# RTC.net
KiCad netlist of a schematic drawn in Altium Designer
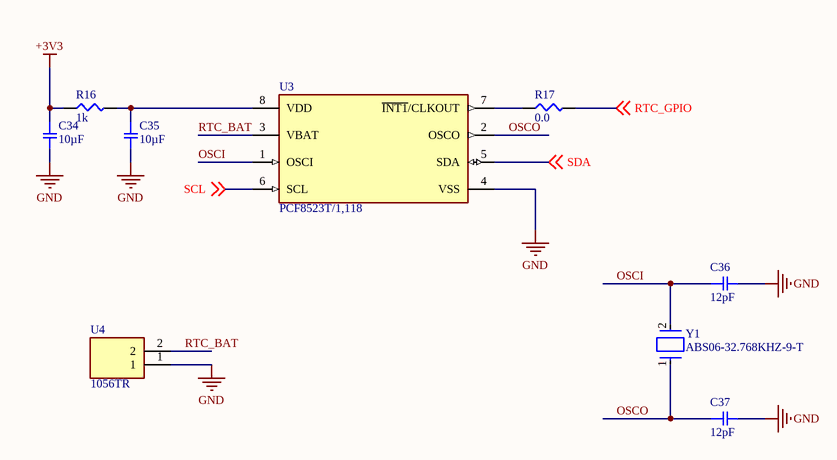
[diagram p0: RTC.SchDoc]

(export (version "E")
  (design (tool "Eeschema 10.0.6"))
  (components
    (comp (ref "C34")
      (value "10µF")
      (footprint "SMD-0402C")
      (description "CAP CER 10UF 6.3V X5R 0402")
      (fields
        (field (name "DIGI-KEY PART NUMBER") "490-13211-1-ND")
        (field (name "PART NUMBER") "GRJ155R60J106ME11D")
      )
      (libsource (lib "capacitor_murata_0402") (part "GRJ155R60J106ME11D"))
    )
    (comp (ref "C35")
      (value "10µF")
      (footprint "SMD-0402C")
      (description "CAP CER 10UF 6.3V X5R 0402")
      (fields
        (field (name "DIGI-KEY PART NUMBER") "490-13211-1-ND")
        (field (name "PART NUMBER") "GRJ155R60J106ME11D")
      )
      (libsource (lib "capacitor_murata_0402") (part "GRJ155R60J106ME11D"))
    )
    (comp (ref "C36")
      (value "12pF")
      (footprint "SMD-0402C")
      (description "CAP CER 12PF 50V NP0 0402")
      (fields
        (field (name "DIGI-KEY PART NUMBER") "490-12649-1-ND")
        (field (name "PART NUMBER") "GCM1555C1H120JA16D")
      )
      (libsource (lib "capacitor_murata_0402") (part "GCM1555C1H120JA16D"))
    )
    (comp (ref "C37")
      (value "12pF")
      (footprint "SMD-0402C")
      (description "CAP CER 12PF 50V NP0 0402")
      (fields
        (field (name "DIGI-KEY PART NUMBER") "490-12649-1-ND")
        (field (name "PART NUMBER") "GCM1555C1H120JA16D")
      )
      (libsource (lib "capacitor_murata_0402") (part "GCM1555C1H120JA16D"))
    )
    (comp (ref "R16")
      (value "1k")
      (footprint "SMD-0402-RES")
      (description "RES SMD 1K OHM 5% 1/10W 0402")
      (fields (field (name "PART NUMBER") "ERJ-2GEJ102X") (field (name "DIGI-KEY PART NUMBER") "P1.0KJCT-ND"))
      (libsource (lib "Panasonic_ERJ_0402") (part "ERJ-2GEJ102X"))
    )
    (comp (ref "R17")
      (value "0.0")
      (footprint "SMD-0402-RES")
      (description "RES SMD 0.0OHM JUMPER 1/10W 0402")
      (fields (field (name "PART NUMBER") "ERJ-2GE0R00X") (field (name "DIGI-KEY PART NUMBER") "P0.0JCT-ND"))
      (libsource (lib "Panasonic_ERJ_0402") (part "ERJ-2GE0R00X"))
    )
    (comp (ref "U3")
      (value "PCF8523T/1,118")
      (footprint "FP-SOT96-1-IPC_B")
      (description "IC RTC CLK/CALENDAR I2C 8-SOIC")
      (libsource (lib "Altium Content Vault") (part "848ef7d52730a566ae52f9242454426"))
    )
    (comp (ref "U4")
      (value "1056TR")
      (footprint "SamacSys:1056TR")
      (description "Undefined or Miscellaneous")
      (fields (field (name "MOUSER PART NUMBER") "534-1056TR"))
      (libsource (lib "*") (part "1056TR"))
    )
    (comp (ref "Y1")
      (value "ABS06-32.768KHZ-9-T")
      (footprint "FP-ABS06-MFG")
      (description "Crystal 32.768kHz ±20ppm (Tol) 9pF FUND 90kΩ 2-Pin Mini-CSMD T/R")
      (fields (field (name "TOLERANCE") "20ppm"))
      (libsource (lib "Altium Content Vault") (part "c23a69dc6c9e2f18f2079038eb95dd1"))
    )
  )
  (nets
    (net (code "1") (name "+3V3") (class "Default")
      (node (ref "C34") (pin "1") (pinfunction "1_1") (pintype "passive"))
      (node (ref "R16") (pin "1") (pinfunction "1_1") (pintype "passive"))
    )
    (net (code "2") (name "/OSCI") (class "Default")
      (node (ref "C36") (pin "1") (pinfunction "1_1") (pintype "passive"))
      (node (ref "U3") (pin "1") (pinfunction "OSCI_1") (pintype "input"))
      (node (ref "Y1") (pin "2") (pinfunction "2_2") (pintype "passive"))
    )
    (net (code "3") (name "/OSCO") (class "Default")
      (node (ref "C37") (pin "1") (pinfunction "1_1") (pintype "passive"))
      (node (ref "U3") (pin "2") (pinfunction "OSCO_2") (pintype "output"))
      (node (ref "Y1") (pin "1") (pinfunction "1_1") (pintype "passive"))
    )
    (net (code "4") (name "/RTC_BAT") (class "Default")
      (node (ref "U3") (pin "3") (pinfunction "VBAT_3") (pintype "power_in"))
      (node (ref "U4") (pin "2") (pinfunction "2_2") (pintype "passive"))
    )
    (net (code "5") (name "GND") (class "Default")
      (node (ref "C34") (pin "2") (pinfunction "2_2") (pintype "passive"))
      (node (ref "C35") (pin "2") (pinfunction "2_2") (pintype "passive"))
      (node (ref "C36") (pin "2") (pinfunction "2_2") (pintype "passive"))
      (node (ref "C37") (pin "2") (pinfunction "2_2") (pintype "passive"))
      (node (ref "U3") (pin "4") (pinfunction "VSS_4") (pintype "power_in"))
      (node (ref "U4") (pin "1") (pinfunction "1_1") (pintype "passive"))
    )
    (net (code "6") (name "Net-(U3-VDD)") (class "Default")
      (node (ref "C35") (pin "1") (pinfunction "1_1") (pintype "passive"))
      (node (ref "R16") (pin "2") (pinfunction "2_2") (pintype "passive"))
      (node (ref "U3") (pin "8") (pinfunction "VDD_8") (pintype "power_in"))
    )
    (net (code "7") (name "Net-(U3-~{INT1}{slash}CLKOUT)") (class "Default")
      (node (ref "R17") (pin "1") (pinfunction "1_1") (pintype "passive"))
      (node (ref "U3") (pin "7") (pinfunction "~{INT1}/CLKOUT_7") (pintype "output"))
    )
    (net (code "8") (name "RTC_GPIO") (class "Default")
      (node (ref "R17") (pin "2") (pinfunction "2_2") (pintype "passive"))
    )
    (net (code "9") (name "SCL") (class "Default")
      (node (ref "U3") (pin "6") (pinfunction "SCL_6") (pintype "input"))
    )
    (net (code "10") (name "SDA") (class "Default")
      (node (ref "U3") (pin "5") (pinfunction "SDA_5") (pintype "bidirectional"))
    )
  )
)
